# KEY.net
KiCad netlist of a schematic drawn in Altium Designer
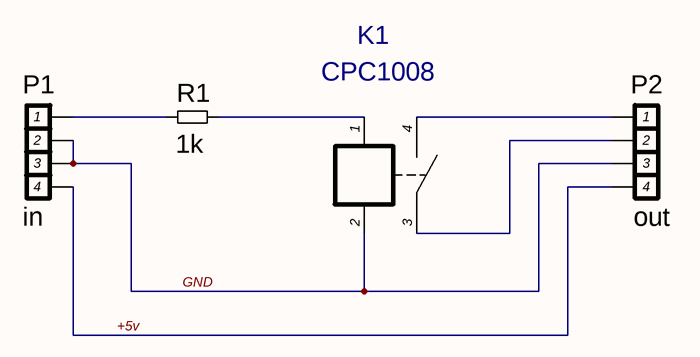
[diagram p0: KEY.SchDoc]

(export (version "E")
  (design (tool "Eeschema 10.0.6"))
  (components
    (comp (ref "K1")
      (value "CPC1008")
      (footprint "SOIC4")
      (description "SSRelay")
      (libsource (lib "DataBase") (part "CPC1008"))
    )
    (comp (ref "P1") (value "in") (footprint "Header 4") (libsource (lib "Connectors") (part "Header 4")))
    (comp (ref "P2") (value "out") (footprint "Header 4") (libsource (lib "Connectors") (part "Header 4")))
    (comp (ref "R1") (value "1k") (footprint "RES_0805") (libsource (lib "Common") (part "Resistor")))
  )
  (nets
    (net (code "1") (name "/+5v") (class "Default")
      (node (ref "P1") (pin "4") (pinfunction "4_4") (pintype "passive"))
      (node (ref "P2") (pin "4") (pinfunction "4_4") (pintype "passive"))
    )
    (net (code "2") (name "/GND") (class "Default")
      (node (ref "K1") (pin "2") (pinfunction "2_2") (pintype "passive"))
      (node (ref "P1") (pin "2") (pinfunction "2_2") (pintype "passive"))
      (node (ref "P1") (pin "3") (pinfunction "3_3") (pintype "passive"))
      (node (ref "P2") (pin "3") (pinfunction "3_3") (pintype "passive"))
    )
    (net (code "3") (name "Net-(K1-Pad1)") (class "Default")
      (node (ref "K1") (pin "1") (pinfunction "1_1") (pintype "passive"))
      (node (ref "R1") (pin "2") (pinfunction "2_2") (pintype "passive"))
    )
    (net (code "4") (name "Net-(K1-Pad3)") (class "Default")
      (node (ref "K1") (pin "3") (pinfunction "3_3") (pintype "passive"))
      (node (ref "P2") (pin "2") (pinfunction "2_2") (pintype "passive"))
    )
    (net (code "5") (name "Net-(K1-Pad4)") (class "Default")
      (node (ref "K1") (pin "4") (pinfunction "4_4") (pintype "passive"))
      (node (ref "P2") (pin "1") (pinfunction "1_1") (pintype "passive"))
    )
    (net (code "6") (name "Net-(P1-Pad1)") (class "Default")
      (node (ref "P1") (pin "1") (pinfunction "1_1") (pintype "passive"))
      (node (ref "R1") (pin "1") (pinfunction "1_1") (pintype "passive"))
    )
  )
)
